# powerboard.net
KiCad netlist of a schematic drawn in EAGLE
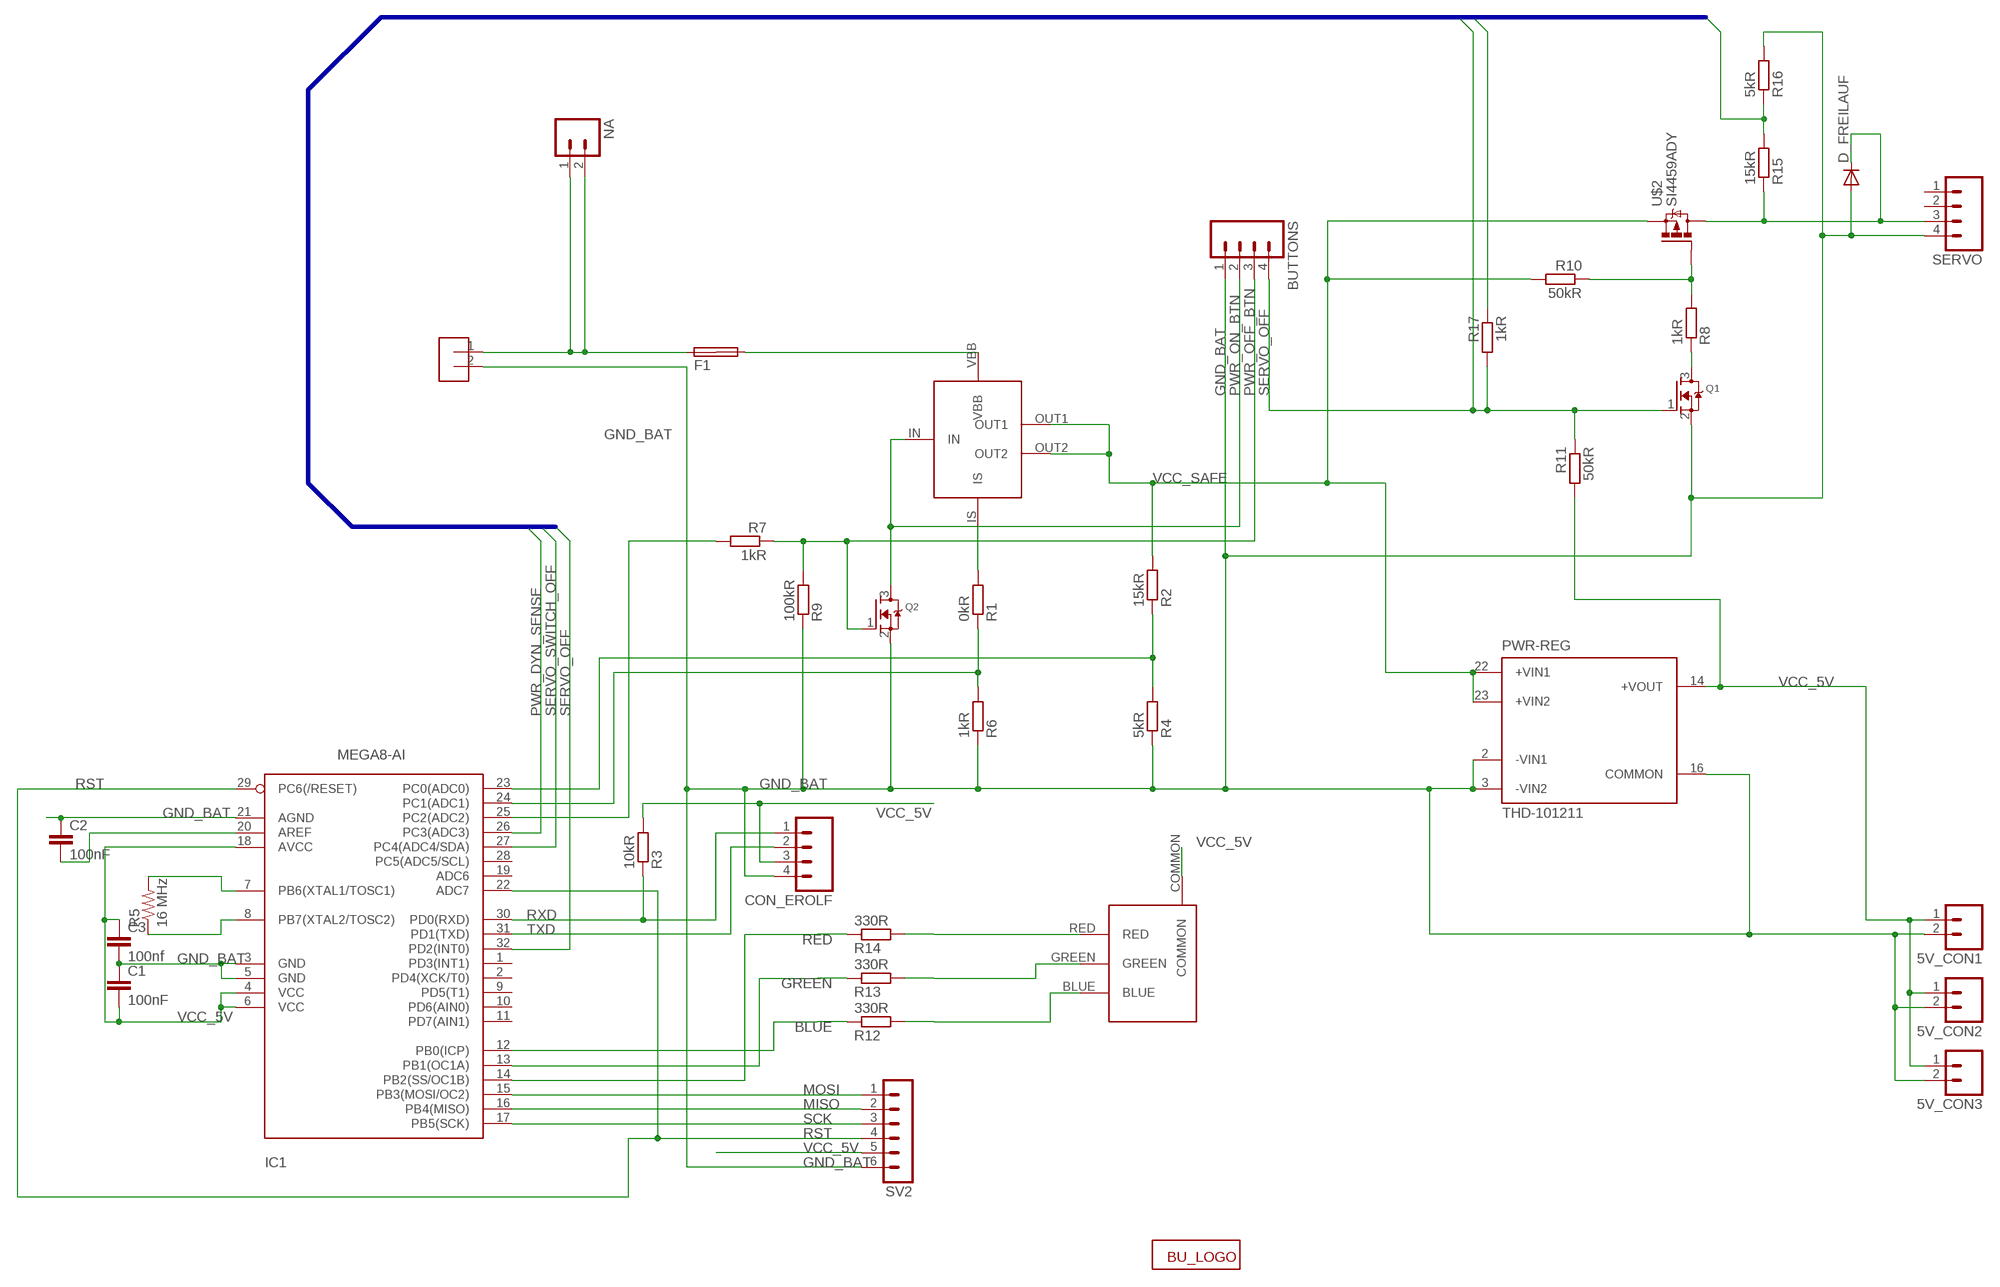
[diagram p0: schematic, sheet 1]

(export (version "E")
  (design (tool "Eeschema 10.0.6"))
  (components
    (comp (ref "5V_CON1")
      (value "M02")
      (footprint "eagle-import:02P")
      (libsource (lib "eagle-import") (part "M02"))
    )
    (comp (ref "5V_CON2")
      (value "M02")
      (footprint "eagle-import:02P")
      (libsource (lib "eagle-import") (part "M02"))
    )
    (comp (ref "5V_CON3")
      (value "M02")
      (footprint "eagle-import:02P")
      (libsource (lib "eagle-import") (part "M02"))
    )
    (comp (ref "BUTTONS")
      (value "M04")
      (footprint "eagle-import:04P")
      (fields (field (name "OC_FARNELL") "unknown") (field (name "OC_NEWARK") "unknown"))
      (libsource (lib "eagle-import") (part "M04"))
    )
    (comp (ref "C1")
      (value "100nF")
      (footprint "eagle-import:C0805")
      (libsource (lib "eagle-import") (part "C-EUC0805"))
    )
    (comp (ref "C2")
      (value "100nF")
      (footprint "eagle-import:C0805")
      (libsource (lib "eagle-import") (part "C-EUC0805"))
    )
    (comp (ref "C3")
      (value "100nf")
      (footprint "eagle-import:C0805")
      (libsource (lib "eagle-import") (part "C-EUC0805"))
    )
    (comp (ref "CON_BAT")
      (value "STROMSTECKER")
      (footprint "eagle-import:STROMSTECKER")
      (libsource (lib "eagle-import") (part "STROMSTECKER"))
    )
    (comp (ref "CON_EROLF")
      (value "M04")
      (footprint "eagle-import:04P")
      (fields (field (name "OC_FARNELL") "unknown") (field (name "OC_NEWARK") "unknown"))
      (libsource (lib "eagle-import") (part "M04"))
    )
    (comp (ref "D_FREILAUF")
      (value "DIODE-DO-214AC")
      (footprint "eagle-import:DO-214AC")
      (libsource (lib "eagle-import") (part "DIODE-DO-214AC"))
    )
    (comp (ref "F1")
      (value "SHK20Q")
      (footprint "eagle-import:SHK20Q")
      (libsource (lib "eagle-import") (part "SHK20Q"))
    )
    (comp (ref "IC1")
      (value "MEGA8-AI")
      (footprint "eagle-import:TQFP32-08")
      (libsource (lib "eagle-import") (part "MEGA8-AI"))
    )
    (comp (ref "NA")
      (value "M02")
      (footprint "eagle-import:02P")
      (fields (field (name "OC_FARNELL") "unknown") (field (name "OC_NEWARK") "unknown"))
      (libsource (lib "eagle-import") (part "M02"))
    )
    (comp (ref "PWR-REG")
      (value "THD-101211")
      (footprint "eagle-import:TEN3XXXX")
      (libsource (lib "eagle-import") (part "TEN_30512"))
    )
    (comp (ref "Q1")
      (value "MOSFET-NREFLOW")
      (footprint "eagle-import:SOT23")
      (libsource (lib "eagle-import") (part "MOSFET-NREFLOW"))
    )
    (comp (ref "Q2")
      (value "MOSFET-NREFLOW")
      (footprint "eagle-import:SOT23")
      (libsource (lib "eagle-import") (part "MOSFET-NREFLOW"))
    )
    (comp (ref "R1")
      (value "0kR")
      (footprint "eagle-import:M0805")
      (libsource (lib "eagle-import") (part "R-EU_M0805"))
    )
    (comp (ref "R2")
      (value "15kR")
      (footprint "eagle-import:M0805")
      (libsource (lib "eagle-import") (part "R-EU_M0805"))
    )
    (comp (ref "R3")
      (value "10kR")
      (footprint "eagle-import:M0805")
      (libsource (lib "eagle-import") (part "R-EU_M0805"))
    )
    (comp (ref "R4")
      (value "5kR")
      (footprint "eagle-import:M0805")
      (libsource (lib "eagle-import") (part "R-EU_M0805"))
    )
    (comp (ref "R5")
      (value "16 MHz")
      (footprint "eagle-import:MINI_MELF-0102W")
      (libsource (lib "eagle-import") (part "R-US_MELF0102W"))
    )
    (comp (ref "R6")
      (value "1kR")
      (footprint "eagle-import:M0805")
      (libsource (lib "eagle-import") (part "R-EU_M0805"))
    )
    (comp (ref "R7")
      (value "1kR")
      (footprint "eagle-import:M0805")
      (libsource (lib "eagle-import") (part "R-EU_M0805"))
    )
    (comp (ref "R8")
      (value "1kR")
      (footprint "eagle-import:M0805")
      (libsource (lib "eagle-import") (part "R-EU_M0805"))
    )
    (comp (ref "R9")
      (value "100kR")
      (footprint "eagle-import:M0805")
      (libsource (lib "eagle-import") (part "R-EU_M0805"))
    )
    (comp (ref "R10")
      (value "50kR")
      (footprint "eagle-import:M0805")
      (libsource (lib "eagle-import") (part "R-EU_M0805"))
    )
    (comp (ref "R11")
      (value "50kR")
      (footprint "eagle-import:M0805")
      (libsource (lib "eagle-import") (part "R-EU_M0805"))
    )
    (comp (ref "R12")
      (value "330R")
      (footprint "eagle-import:M0805")
      (libsource (lib "eagle-import") (part "R-EU_M0805"))
    )
    (comp (ref "R13")
      (value "330R")
      (footprint "eagle-import:M0805")
      (libsource (lib "eagle-import") (part "R-EU_M0805"))
    )
    (comp (ref "R14")
      (value "330R")
      (footprint "eagle-import:M0805")
      (libsource (lib "eagle-import") (part "R-EU_M0805"))
    )
    (comp (ref "R15")
      (value "15kR")
      (footprint "eagle-import:M0805")
      (libsource (lib "eagle-import") (part "R-EU_M0805"))
    )
    (comp (ref "R16")
      (value "5kR")
      (footprint "eagle-import:M0805")
      (libsource (lib "eagle-import") (part "R-EU_M0805"))
    )
    (comp (ref "R17")
      (value "1kR")
      (footprint "eagle-import:M0805")
      (libsource (lib "eagle-import") (part "R-EU_M0805"))
    )
    (comp (ref "SERVO")
      (value "M04")
      (footprint "eagle-import:04P")
      (libsource (lib "eagle-import") (part "M04"))
    )
    (comp (ref "SV2")
      (value "MA06-1")
      (footprint "eagle-import:MA06-1")
      (libsource (lib "eagle-import") (part "MA06-1"))
    )
    (comp (ref "U$1")
      (value "BTS555")
      (footprint "eagle-import:PG-TO218")
      (libsource (lib "eagle-import") (part "BTS555"))
    )
    (comp (ref "U$2")
      (value "SI4459ADY")
      (footprint "eagle-import:SO-8")
      (libsource (lib "eagle-import") (part "SI4459ADY"))
    )
    (comp (ref "U$3")
      (value "RGB-LED")
      (footprint "eagle-import:4-PLCC")
      (libsource (lib "eagle-import") (part "RGB-LED"))
    )
    (comp (ref "U$4")
      (value "LOGO")
      (footprint "eagle-import:LOGO")
      (libsource (lib "eagle-import") (part "LOGO"))
    )
  )
  (nets
    (net (code "1") (name "/BLUE") (class "Default")
      (node (ref "IC1") (pin "12") (pinfunction "PB0(ICP)_12") (pintype "bidirectional"))
      (node (ref "R12") (pin "1") (pinfunction "1_1") (pintype "passive"))
    )
    (net (code "2") (name "/GND_BAT") (class "Default")
      (node (ref "5V_CON1") (pin "2") (pinfunction "2_2") (pintype "passive"))
      (node (ref "5V_CON2") (pin "2") (pinfunction "2_2") (pintype "passive"))
      (node (ref "5V_CON3") (pin "2") (pinfunction "2_2") (pintype "passive"))
      (node (ref "BUTTONS") (pin "1") (pinfunction "1_1") (pintype "passive"))
      (node (ref "C1") (pin "1") (pinfunction "1_1") (pintype "passive"))
      (node (ref "C2") (pin "1") (pinfunction "1_1") (pintype "passive"))
      (node (ref "C3") (pin "2") (pinfunction "2_2") (pintype "passive"))
      (node (ref "CON_BAT") (pin "2") (pinfunction "2_2") (pintype "bidirectional"))
      (node (ref "CON_EROLF") (pin "4") (pinfunction "4_4") (pintype "passive"))
      (node (ref "D_FREILAUF") (pin "A") (pinfunction "A_A") (pintype "passive"))
      (node (ref "IC1") (pin "21") (pinfunction "AGND_21") (pintype "bidirectional"))
      (node (ref "IC1") (pin "3") (pinfunction "GND_3") (pintype "bidirectional"))
      (node (ref "IC1") (pin "5") (pinfunction "GND_5") (pintype "bidirectional"))
      (node (ref "PWR-REG") (pin "16") (pinfunction "COMMON_16") (pintype "passive"))
      (node (ref "PWR-REG") (pin "2") (pinfunction "-VIN1_2") (pintype "input"))
      (node (ref "PWR-REG") (pin "3") (pinfunction "-VIN2_3") (pintype "input"))
      (node (ref "Q1") (pin "2") (pinfunction "S_2") (pintype "bidirectional"))
      (node (ref "Q2") (pin "2") (pinfunction "S_2") (pintype "bidirectional"))
      (node (ref "R16") (pin "2") (pinfunction "2_2") (pintype "passive"))
      (node (ref "R4") (pin "1") (pinfunction "1_1") (pintype "passive"))
      (node (ref "R6") (pin "1") (pinfunction "1_1") (pintype "passive"))
      (node (ref "R9") (pin "1") (pinfunction "1_1") (pintype "passive"))
      (node (ref "SERVO") (pin "4") (pinfunction "4_4") (pintype "passive"))
      (node (ref "SV2") (pin "6") (pinfunction "6_6") (pintype "passive"))
    )
    (net (code "3") (name "/GREEN") (class "Default")
      (node (ref "IC1") (pin "13") (pinfunction "PB1(OC1A)_13") (pintype "bidirectional"))
      (node (ref "R13") (pin "1") (pinfunction "1_1") (pintype "passive"))
    )
    (net (code "4") (name "/MISO") (class "Default")
      (node (ref "IC1") (pin "16") (pinfunction "PB4(MISO)_16") (pintype "bidirectional"))
      (node (ref "SV2") (pin "2") (pinfunction "2_2") (pintype "passive"))
    )
    (net (code "5") (name "/MOSI") (class "Default")
      (node (ref "IC1") (pin "15") (pinfunction "PB3(MOSI/OC2)_15") (pintype "bidirectional"))
      (node (ref "SV2") (pin "1") (pinfunction "1_1") (pintype "passive"))
    )
    (net (code "6") (name "/PWR_DYN_SENSE") (class "Default")
      (node (ref "IC1") (pin "26") (pinfunction "PC3(ADC3)_26") (pintype "bidirectional"))
      (node (ref "R15") (pin "2") (pinfunction "2_2") (pintype "passive"))
      (node (ref "R16") (pin "1") (pinfunction "1_1") (pintype "passive"))
    )
    (net (code "7") (name "/PWR_OFF_BTN") (class "Default")
      (node (ref "BUTTONS") (pin "3") (pinfunction "3_3") (pintype "passive"))
      (node (ref "Q2") (pin "1") (pinfunction "G_1") (pintype "bidirectional"))
      (node (ref "R7") (pin "1") (pinfunction "1_1") (pintype "passive"))
      (node (ref "R9") (pin "2") (pinfunction "2_2") (pintype "passive"))
    )
    (net (code "8") (name "/PWR_ON_BTN") (class "Default")
      (node (ref "BUTTONS") (pin "2") (pinfunction "2_2") (pintype "passive"))
      (node (ref "Q2") (pin "3") (pinfunction "D_3") (pintype "bidirectional"))
      (node (ref "U$1") (pin "IN") (pinfunction "IN_IN") (pintype "bidirectional"))
    )
    (net (code "9") (name "/RED") (class "Default")
      (node (ref "IC1") (pin "14") (pinfunction "PB2(SS/OC1B)_14") (pintype "bidirectional"))
      (node (ref "R14") (pin "1") (pinfunction "1_1") (pintype "passive"))
    )
    (net (code "10") (name "/RST") (class "Default")
      (node (ref "IC1") (pin "22") (pinfunction "ADC7_22") (pintype "bidirectional"))
      (node (ref "IC1") (pin "29") (pinfunction "PC6(/RESET)_29") (pintype "bidirectional"))
      (node (ref "SV2") (pin "4") (pinfunction "4_4") (pintype "passive"))
    )
    (net (code "11") (name "/RXD") (class "Default")
      (node (ref "CON_EROLF") (pin "1") (pinfunction "1_1") (pintype "passive"))
      (node (ref "IC1") (pin "30") (pinfunction "PD0(RXD)_30") (pintype "bidirectional"))
      (node (ref "R3") (pin "1") (pinfunction "1_1") (pintype "passive"))
    )
    (net (code "12") (name "/SCK") (class "Default")
      (node (ref "IC1") (pin "17") (pinfunction "PB5(SCK)_17") (pintype "bidirectional"))
      (node (ref "SV2") (pin "3") (pinfunction "3_3") (pintype "passive"))
    )
    (net (code "13") (name "/SERVO_OFF") (class "Default")
      (node (ref "BUTTONS") (pin "4") (pinfunction "4_4") (pintype "passive"))
      (node (ref "IC1") (pin "32") (pinfunction "PD2(INT0)_32") (pintype "bidirectional"))
      (node (ref "Q1") (pin "1") (pinfunction "G_1") (pintype "bidirectional"))
      (node (ref "R11") (pin "1") (pinfunction "1_1") (pintype "passive"))
      (node (ref "R17") (pin "2") (pinfunction "2_2") (pintype "passive"))
    )
    (net (code "14") (name "/SERVO_SWITCH_OFF") (class "Default")
      (node (ref "IC1") (pin "27") (pinfunction "PC4(ADC4/SDA)_27") (pintype "bidirectional"))
      (node (ref "R17") (pin "1") (pinfunction "1_1") (pintype "passive"))
    )
    (net (code "15") (name "/TXD") (class "Default")
      (node (ref "CON_EROLF") (pin "2") (pinfunction "2_2") (pintype "passive"))
      (node (ref "IC1") (pin "31") (pinfunction "PD1(TXD)_31") (pintype "bidirectional"))
    )
    (net (code "16") (name "/VCC_5V") (class "Default")
      (node (ref "5V_CON1") (pin "1") (pinfunction "1_1") (pintype "passive"))
      (node (ref "5V_CON2") (pin "1") (pinfunction "1_1") (pintype "passive"))
      (node (ref "5V_CON3") (pin "1") (pinfunction "1_1") (pintype "passive"))
      (node (ref "C1") (pin "2") (pinfunction "2_2") (pintype "passive"))
      (node (ref "C3") (pin "1") (pinfunction "1_1") (pintype "passive"))
      (node (ref "CON_EROLF") (pin "3") (pinfunction "3_3") (pintype "passive"))
      (node (ref "IC1") (pin "18") (pinfunction "AVCC_18") (pintype "bidirectional"))
      (node (ref "IC1") (pin "4") (pinfunction "VCC_4") (pintype "bidirectional"))
      (node (ref "IC1") (pin "6") (pinfunction "VCC_6") (pintype "bidirectional"))
      (node (ref "PWR-REG") (pin "14") (pinfunction "+VOUT_14") (pintype "passive"))
      (node (ref "R11") (pin "2") (pinfunction "2_2") (pintype "passive"))
      (node (ref "R3") (pin "2") (pinfunction "2_2") (pintype "passive"))
      (node (ref "SV2") (pin "5") (pinfunction "5_5") (pintype "passive"))
      (node (ref "U$3") (pin "COMMON") (pinfunction "COMMON_COMMON") (pintype "bidirectional"))
    )
    (net (code "17") (name "/VCC_SAFE") (class "Default")
      (node (ref "PWR-REG") (pin "22") (pinfunction "+VIN1_22") (pintype "input"))
      (node (ref "PWR-REG") (pin "23") (pinfunction "+VIN2_23") (pintype "input"))
      (node (ref "R10") (pin "2") (pinfunction "2_2") (pintype "passive"))
      (node (ref "R2") (pin "2") (pinfunction "2_2") (pintype "passive"))
      (node (ref "U$1") (pin "OUT1") (pinfunction "OUT1_OUT1") (pintype "bidirectional"))
      (node (ref "U$1") (pin "OUT2") (pinfunction "OUT2_OUT2") (pintype "bidirectional"))
      (node (ref "U$2") (pin "P1") (pinfunction "S_P1") (pintype "passive"))
      (node (ref "U$2") (pin "P2") (pinfunction "S_P2") (pintype "passive"))
      (node (ref "U$2") (pin "P3") (pinfunction "S_P3") (pintype "passive"))
    )
    (net (code "18") (name "Net-(CON_BAT-Pad1)") (class "Default")
      (node (ref "CON_BAT") (pin "1") (pinfunction "1_1") (pintype "bidirectional"))
      (node (ref "F1") (pin "1A") (pinfunction "1A_1A") (pintype "passive"))
      (node (ref "NA") (pin "1") (pinfunction "1_1") (pintype "passive"))
      (node (ref "NA") (pin "2") (pinfunction "2_2") (pintype "passive"))
    )
    (net (code "19") (name "Net-(D_FREILAUF-PadC)") (class "Default")
      (node (ref "D_FREILAUF") (pin "C") (pinfunction "C_C") (pintype "passive"))
      (node (ref "R15") (pin "1") (pinfunction "1_1") (pintype "passive"))
      (node (ref "SERVO") (pin "3") (pinfunction "3_3") (pintype "passive"))
      (node (ref "U$2") (pin "P5") (pinfunction "D_P5") (pintype "passive"))
      (node (ref "U$2") (pin "P6") (pinfunction "D_P6") (pintype "passive"))
      (node (ref "U$2") (pin "P7") (pinfunction "D_P7") (pintype "passive"))
      (node (ref "U$2") (pin "P8") (pinfunction "D_P8") (pintype "passive"))
    )
    (net (code "20") (name "Net-(F1-Pad2A)") (class "Default")
      (node (ref "F1") (pin "2A") (pinfunction "2A_2A") (pintype "passive"))
      (node (ref "U$1") (pin "VBB") (pinfunction "VBB_VBB") (pintype "bidirectional"))
    )
    (net (code "21") (name "Net-(IC1-AREF)") (class "Default")
      (node (ref "C2") (pin "2") (pinfunction "2_2") (pintype "passive"))
      (node (ref "IC1") (pin "20") (pinfunction "AREF_20") (pintype "bidirectional"))
    )
    (net (code "22") (name "Net-(IC1-PB6(XTAL1{slash}TOSC1))") (class "Default")
      (node (ref "IC1") (pin "7") (pinfunction "PB6(XTAL1/TOSC1)_7") (pintype "bidirectional"))
      (node (ref "R5") (pin "2") (pinfunction "2_2") (pintype "passive"))
    )
    (net (code "23") (name "Net-(IC1-PB7(XTAL2{slash}TOSC2))") (class "Default")
      (node (ref "IC1") (pin "8") (pinfunction "PB7(XTAL2/TOSC2)_8") (pintype "bidirectional"))
      (node (ref "R5") (pin "1") (pinfunction "1_1") (pintype "passive"))
    )
    (net (code "24") (name "Net-(IC1-PC0(ADC0))") (class "Default")
      (node (ref "IC1") (pin "23") (pinfunction "PC0(ADC0)_23") (pintype "bidirectional"))
      (node (ref "R2") (pin "1") (pinfunction "1_1") (pintype "passive"))
      (node (ref "R4") (pin "2") (pinfunction "2_2") (pintype "passive"))
    )
    (net (code "25") (name "Net-(IC1-PC1(ADC1))") (class "Default")
      (node (ref "IC1") (pin "24") (pinfunction "PC1(ADC1)_24") (pintype "bidirectional"))
      (node (ref "R1") (pin "1") (pinfunction "1_1") (pintype "passive"))
      (node (ref "R6") (pin "2") (pinfunction "2_2") (pintype "passive"))
    )
    (net (code "26") (name "Net-(IC1-PC2(ADC2))") (class "Default")
      (node (ref "IC1") (pin "25") (pinfunction "PC2(ADC2)_25") (pintype "bidirectional"))
      (node (ref "R7") (pin "2") (pinfunction "2_2") (pintype "passive"))
    )
    (net (code "27") (name "Net-(Q1-D)") (class "Default")
      (node (ref "Q1") (pin "3") (pinfunction "D_3") (pintype "bidirectional"))
      (node (ref "R8") (pin "1") (pinfunction "1_1") (pintype "passive"))
    )
    (net (code "28") (name "Net-(R1-Pad2)") (class "Default")
      (node (ref "R1") (pin "2") (pinfunction "2_2") (pintype "passive"))
      (node (ref "U$1") (pin "IS") (pinfunction "IS_IS") (pintype "bidirectional"))
    )
    (net (code "29") (name "Net-(R12-Pad2)") (class "Default")
      (node (ref "R12") (pin "2") (pinfunction "2_2") (pintype "passive"))
      (node (ref "U$3") (pin "BLUE") (pinfunction "BLUE_BLUE") (pintype "bidirectional"))
    )
    (net (code "30") (name "Net-(R13-Pad2)") (class "Default")
      (node (ref "R13") (pin "2") (pinfunction "2_2") (pintype "passive"))
      (node (ref "U$3") (pin "GREEN") (pinfunction "GREEN_GREEN") (pintype "bidirectional"))
    )
    (net (code "31") (name "Net-(R14-Pad2)") (class "Default")
      (node (ref "R14") (pin "2") (pinfunction "2_2") (pintype "passive"))
      (node (ref "U$3") (pin "RED") (pinfunction "RED_RED") (pintype "bidirectional"))
    )
    (net (code "32") (name "Net-(U$2-G)") (class "Default")
      (node (ref "R10") (pin "1") (pinfunction "1_1") (pintype "passive"))
      (node (ref "R8") (pin "2") (pinfunction "2_2") (pintype "passive"))
      (node (ref "U$2") (pin "P4") (pinfunction "G_P4") (pintype "passive"))
    )
    (net (code "33") (name "unconnected-(F1-Pad1B)") (class "Default")
      (node (ref "F1") (pin "1B") (pinfunction "1B_1B") (pintype "passive"))
    )
    (net (code "34") (name "unconnected-(F1-Pad2B)") (class "Default")
      (node (ref "F1") (pin "2B") (pinfunction "2B_2B") (pintype "passive"))
    )
    (net (code "35") (name "unconnected-(IC1-ADC6-Pad19)") (class "Default")
      (node (ref "IC1") (pin "19") (pinfunction "ADC6_19") (pintype "bidirectional"))
    )
    (net (code "36") (name "unconnected-(IC1-PC5(ADC5{slash}SCL)-Pad28)") (class "Default")
      (node (ref "IC1") (pin "28") (pinfunction "PC5(ADC5/SCL)_28") (pintype "bidirectional"))
    )
    (net (code "37") (name "unconnected-(IC1-PD3(INT1)-Pad1)") (class "Default")
      (node (ref "IC1") (pin "1") (pinfunction "PD3(INT1)_1") (pintype "bidirectional"))
    )
    (net (code "38") (name "unconnected-(IC1-PD4(XCK{slash}T0)-Pad2)") (class "Default")
      (node (ref "IC1") (pin "2") (pinfunction "PD4(XCK/T0)_2") (pintype "bidirectional"))
    )
    (net (code "39") (name "unconnected-(IC1-PD5(T1)-Pad9)") (class "Default")
      (node (ref "IC1") (pin "9") (pinfunction "PD5(T1)_9") (pintype "bidirectional"))
    )
    (net (code "40") (name "unconnected-(IC1-PD6(AIN0)-Pad10)") (class "Default")
      (node (ref "IC1") (pin "10") (pinfunction "PD6(AIN0)_10") (pintype "bidirectional"))
    )
    (net (code "41") (name "unconnected-(IC1-PD7(AIN1)-Pad11)") (class "Default")
      (node (ref "IC1") (pin "11") (pinfunction "PD7(AIN1)_11") (pintype "bidirectional"))
    )
    (net (code "42") (name "unconnected-(SERVO-Pad1)") (class "Default")
      (node (ref "SERVO") (pin "1") (pinfunction "1_1") (pintype "passive"))
    )
    (net (code "43") (name "unconnected-(SERVO-Pad2)") (class "Default")
      (node (ref "SERVO") (pin "2") (pinfunction "2_2") (pintype "passive"))
    )
  )
)
